# Adafruit_QSPI_DIP_Breakout.net
KiCad netlist of a schematic drawn in EAGLE
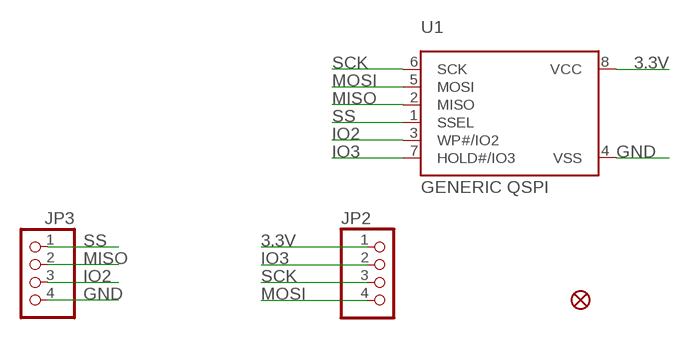
[diagram p0: schematic, sheet 1]

(export (version "E")
  (design (tool "Eeschema 10.0.6"))
  (components
    (comp (ref "FID1")
      (value "FIDUCIAL_1MM")
      (footprint "eagle-import:FIDUCIAL_1MM")
      (libsource (lib "eagle-import") (part "FIDUCIAL_1MM"))
    )
    (comp (ref "JP2")
      (value "HEADER-1X476MIL")
      (footprint "eagle-import:1X04_ROUND_76")
      (libsource (lib "eagle-import") (part "HEADER-1X476MIL"))
    )
    (comp (ref "JP3")
      (value "HEADER-1X476MIL")
      (footprint "eagle-import:1X04_ROUND_76")
      (libsource (lib "eagle-import") (part "HEADER-1X476MIL"))
    )
    (comp (ref "U1")
      (value "GENERIC QSPI")
      (footprint "eagle-import:SOIC8_208MIL")
      (libsource (lib "eagle-import") (part "SPIFLASH_8PIN208MIL"))
    )
  )
  (nets
    (net (code "1") (name "/3.3V") (class "Default")
      (node (ref "JP2") (pin "1") (pinfunction "1_1") (pintype "passive"))
      (node (ref "U1") (pin "8") (pinfunction "VCC_8") (pintype "bidirectional"))
    )
    (net (code "2") (name "/GND") (class "Default")
      (node (ref "JP3") (pin "4") (pinfunction "4_4") (pintype "passive"))
      (node (ref "U1") (pin "4") (pinfunction "VSS_4") (pintype "bidirectional"))
    )
    (net (code "3") (name "/IO2") (class "Default")
      (node (ref "JP3") (pin "3") (pinfunction "3_3") (pintype "passive"))
      (node (ref "U1") (pin "3") (pinfunction "WP#/IO2_3") (pintype "bidirectional"))
    )
    (net (code "4") (name "/IO3") (class "Default")
      (node (ref "JP2") (pin "2") (pinfunction "2_2") (pintype "passive"))
      (node (ref "U1") (pin "7") (pinfunction "HOLD#/IO3_7") (pintype "bidirectional"))
    )
    (net (code "5") (name "/MISO") (class "Default")
      (node (ref "JP3") (pin "2") (pinfunction "2_2") (pintype "passive"))
      (node (ref "U1") (pin "2") (pinfunction "MISO_2") (pintype "bidirectional"))
    )
    (net (code "6") (name "/MOSI") (class "Default")
      (node (ref "JP2") (pin "4") (pinfunction "4_4") (pintype "passive"))
      (node (ref "U1") (pin "5") (pinfunction "MOSI_5") (pintype "bidirectional"))
    )
    (net (code "7") (name "/SCK") (class "Default")
      (node (ref "JP2") (pin "3") (pinfunction "3_3") (pintype "passive"))
      (node (ref "U1") (pin "6") (pinfunction "SCK_6") (pintype "bidirectional"))
    )
    (net (code "8") (name "/SS") (class "Default")
      (node (ref "JP3") (pin "1") (pinfunction "1_1") (pintype "passive"))
      (node (ref "U1") (pin "1") (pinfunction "SSEL_1") (pintype "bidirectional"))
    )
  )
)
